# sheet2.net
KiCad netlist of a schematic drawn in Altium Designer
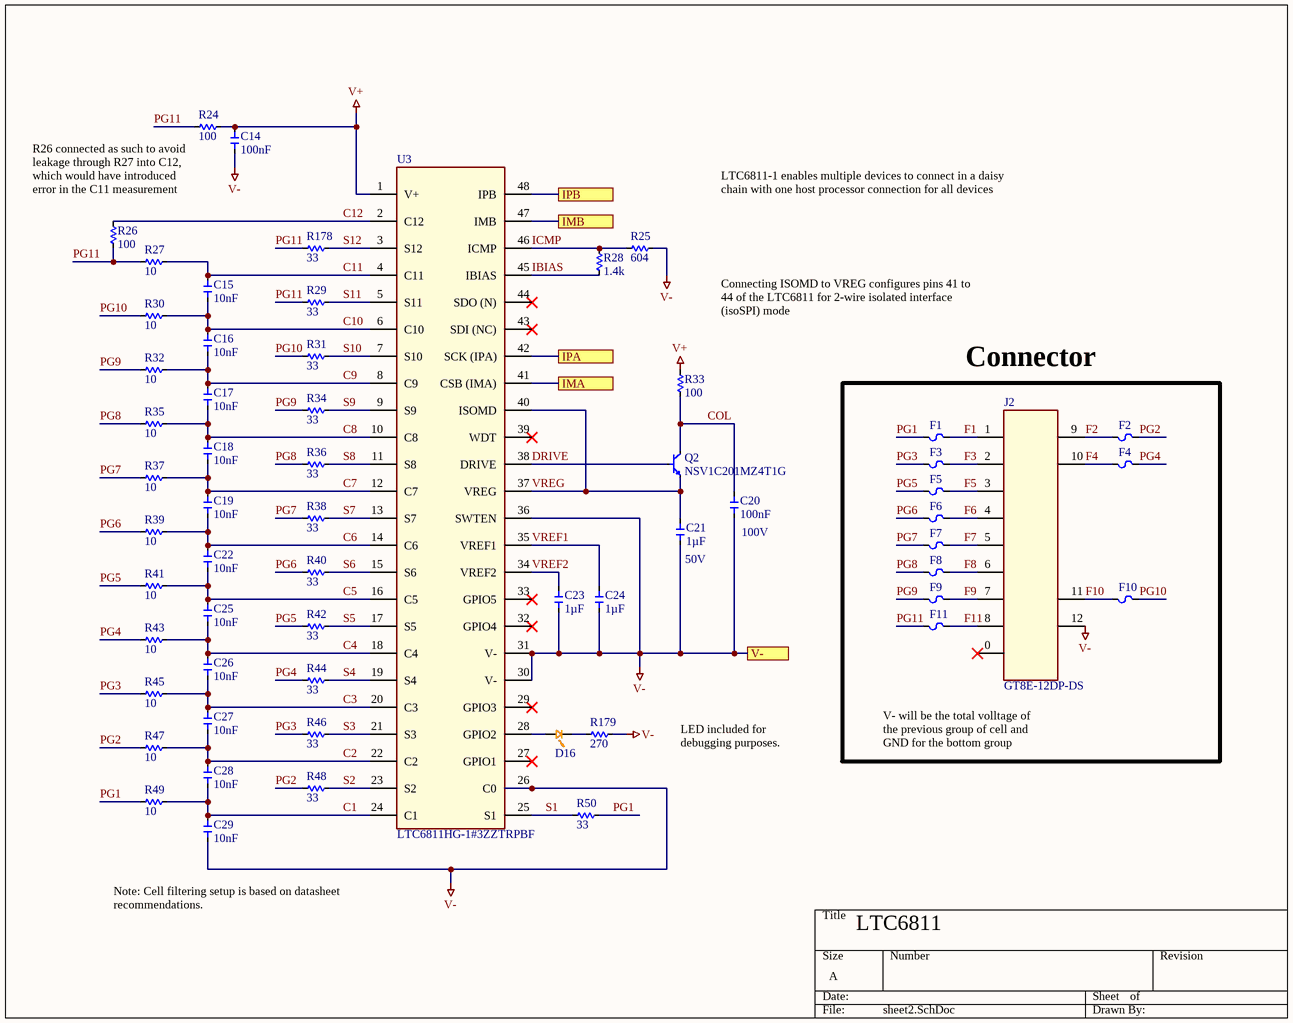
[diagram p0: sheet2.SchDoc]

(export (version "E")
  (design (tool "Eeschema 10.0.6"))
  (components
    (comp (ref "C14")
      (value "100nF")
      (footprint "C0603_0.80MM")
      (description "CAP CER 0.1UF 100V X7S 0603")
      (fields
        (field (name "MANUFACTURER PART NUMBER") "CGJ3E3X7S2A104K080AA")
        (field (name "MANUFACTURER") "TDK Corporation")
      )
      (libsource (lib "Stanford Solar Car Project") (part "2pin_nonpolar_capacitor"))
    )
    (comp (ref "C15")
      (value "10nF")
      (footprint "C0603_0.90MM")
      (description "CAP CER 10000PF 50V C0G 0603")
      (fields (field (name "MANUFACTURER") "TDK Corporation") (field (name "TOLERANCE") "5%"))
      (libsource (lib "Stanford Solar Car Project") (part "2pin_nonpolar_capacitor"))
    )
    (comp (ref "C16")
      (value "10nF")
      (footprint "C0603_0.90MM")
      (description "CAP CER 10000PF 50V C0G 0603")
      (fields (field (name "MANUFACTURER") "TDK Corporation") (field (name "TOLERANCE") "5%"))
      (libsource (lib "Stanford Solar Car Project") (part "2pin_nonpolar_capacitor"))
    )
    (comp (ref "C17")
      (value "10nF")
      (footprint "C0603_0.90MM")
      (description "CAP CER 10000PF 50V C0G 0603")
      (fields (field (name "MANUFACTURER") "TDK Corporation") (field (name "TOLERANCE") "5%"))
      (libsource (lib "Stanford Solar Car Project") (part "2pin_nonpolar_capacitor"))
    )
    (comp (ref "C18")
      (value "10nF")
      (footprint "C0603_0.90MM")
      (description "CAP CER 10000PF 50V C0G 0603")
      (fields (field (name "MANUFACTURER") "TDK Corporation") (field (name "TOLERANCE") "5%"))
      (libsource (lib "Stanford Solar Car Project") (part "2pin_nonpolar_capacitor"))
    )
    (comp (ref "C19")
      (value "10nF")
      (footprint "C0603_0.90MM")
      (description "CAP CER 10000PF 50V C0G 0603")
      (fields (field (name "MANUFACTURER") "TDK Corporation") (field (name "TOLERANCE") "5%"))
      (libsource (lib "Stanford Solar Car Project") (part "2pin_nonpolar_capacitor"))
    )
    (comp (ref "C20")
      (value "100nF")
      (footprint "C0603_0.80MM")
      (description "CAP CER 0.1UF 100V X7S 0603")
      (fields
        (field (name "VOLTAGE - RATED") "100V")
        (field (name "MANUFACTURER PART NUMBER") "CGJ3E3X7S2A104K080AA")
        (field (name "MANUFACTURER") "TDK Corporation")
      )
      (libsource (lib "Stanford Solar Car Project") (part "2pin_nonpolar_capacitor"))
    )
    (comp (ref "C21")
      (value "1µF")
      (footprint "C0805_1.45MM")
      (description "CAP CER 1UF 50V X5R 0805")
      (fields
        (field (name "VOLTAGE - RATED") "50V")
        (field (name "MANUFACTURER") "TDK Corporation")
        (field (name "DIGI-KEY PART NUMBER") "445-12703-1-ND")
      )
      (libsource (lib "Stanford Solar Car Project") (part "2pin_nonpolar_capacitor"))
    )
    (comp (ref "C22")
      (value "10nF")
      (footprint "C0603_0.90MM")
      (description "CAP CER 10000PF 50V C0G 0603")
      (fields (field (name "MANUFACTURER") "TDK Corporation") (field (name "TOLERANCE") "5%"))
      (libsource (lib "Stanford Solar Car Project") (part "2pin_nonpolar_capacitor"))
    )
    (comp (ref "C23")
      (value "1µF")
      (footprint "C0805_1.45MM")
      (description "CAP CER 1UF 50V X5R 0805")
      (fields
        (field (name "MANUFACTURER") "TDK Corporation")
        (field (name "DIGI-KEY PART NUMBER") "445-12703-1-ND")
      )
      (libsource (lib "Stanford Solar Car Project") (part "2pin_nonpolar_capacitor"))
    )
    (comp (ref "C24")
      (value "1µF")
      (footprint "C0805_1.45MM")
      (description "CAP CER 1UF 50V X5R 0805")
      (fields
        (field (name "MANUFACTURER") "TDK Corporation")
        (field (name "DIGI-KEY PART NUMBER") "445-12703-1-ND")
      )
      (libsource (lib "Stanford Solar Car Project") (part "2pin_nonpolar_capacitor"))
    )
    (comp (ref "C25")
      (value "10nF")
      (footprint "C0603_0.90MM")
      (description "CAP CER 10000PF 50V C0G 0603")
      (fields (field (name "MANUFACTURER") "TDK Corporation") (field (name "TOLERANCE") "5%"))
      (libsource (lib "Stanford Solar Car Project") (part "2pin_nonpolar_capacitor"))
    )
    (comp (ref "C26")
      (value "10nF")
      (footprint "C0603_0.90MM")
      (description "CAP CER 10000PF 50V C0G 0603")
      (fields (field (name "MANUFACTURER") "TDK Corporation") (field (name "TOLERANCE") "5%"))
      (libsource (lib "Stanford Solar Car Project") (part "2pin_nonpolar_capacitor"))
    )
    (comp (ref "C27")
      (value "10nF")
      (footprint "C0603_0.90MM")
      (description "CAP CER 10000PF 50V C0G 0603")
      (fields (field (name "MANUFACTURER") "TDK Corporation") (field (name "TOLERANCE") "5%"))
      (libsource (lib "Stanford Solar Car Project") (part "2pin_nonpolar_capacitor"))
    )
    (comp (ref "C28")
      (value "10nF")
      (footprint "C0603_0.90MM")
      (description "CAP CER 10000PF 50V C0G 0603")
      (fields (field (name "MANUFACTURER") "TDK Corporation") (field (name "TOLERANCE") "5%"))
      (libsource (lib "Stanford Solar Car Project") (part "2pin_nonpolar_capacitor"))
    )
    (comp (ref "C29")
      (value "10nF")
      (footprint "C0603_0.90MM")
      (description "CAP CER 10000PF 50V C0G 0603")
      (fields (field (name "MANUFACTURER") "TDK Corporation") (field (name "TOLERANCE") "5%"))
      (libsource (lib "Stanford Solar Car Project") (part "2pin_nonpolar_capacitor"))
    )
    (comp (ref "D16")
      (value "LTST-C194KFKT")
      (footprint "LED_0603P_ORANGE")
      (description "LED ORANGE CLEAR SMD")
      (libsource (lib "Stanford Solar Car Project") (part "_template_led_orange"))
    )
    (comp (ref "F1")
      (value "C2Q 250")
      (footprint "R0603_0.50MM")
      (description "FUSE BOARD MNT 250MA 32VAC 63VDC")
      (fields
        (field (name "MANUFACTURER") "Bel Fuse Inc.")
        (field (name "DIGI-KEY PART NUMBER") "507-1086-1-ND")
      )
      (libsource (lib "sscp") (part "_template_fuse"))
    )
    (comp (ref "F2")
      (value "C2Q 250")
      (footprint "R0603_0.50MM")
      (description "FUSE BOARD MNT 250MA 32VAC 63VDC")
      (fields
        (field (name "MANUFACTURER") "Bel Fuse Inc.")
        (field (name "DIGI-KEY PART NUMBER") "507-1086-1-ND")
      )
      (libsource (lib "sscp") (part "_template_fuse"))
    )
    (comp (ref "F3")
      (value "C2Q 250")
      (footprint "R0603_0.50MM")
      (description "FUSE BOARD MNT 250MA 32VAC 63VDC")
      (fields
        (field (name "MANUFACTURER") "Bel Fuse Inc.")
        (field (name "DIGI-KEY PART NUMBER") "507-1086-1-ND")
      )
      (libsource (lib "sscp") (part "_template_fuse"))
    )
    (comp (ref "F4")
      (value "C2Q 250")
      (footprint "R0603_0.50MM")
      (description "FUSE BOARD MNT 250MA 32VAC 63VDC")
      (fields
        (field (name "MANUFACTURER") "Bel Fuse Inc.")
        (field (name "DIGI-KEY PART NUMBER") "507-1086-1-ND")
      )
      (libsource (lib "sscp") (part "_template_fuse"))
    )
    (comp (ref "F5")
      (value "C2Q 250")
      (footprint "R0603_0.50MM")
      (description "FUSE BOARD MNT 250MA 32VAC 63VDC")
      (fields
        (field (name "MANUFACTURER") "Bel Fuse Inc.")
        (field (name "DIGI-KEY PART NUMBER") "507-1086-1-ND")
      )
      (libsource (lib "sscp") (part "_template_fuse"))
    )
    (comp (ref "F6")
      (value "C2Q 250")
      (footprint "R0603_0.50MM")
      (description "FUSE BOARD MNT 250MA 32VAC 63VDC")
      (fields
        (field (name "MANUFACTURER") "Bel Fuse Inc.")
        (field (name "DIGI-KEY PART NUMBER") "507-1086-1-ND")
      )
      (libsource (lib "sscp") (part "_template_fuse"))
    )
    (comp (ref "F7")
      (value "C2Q 250")
      (footprint "R0603_0.50MM")
      (description "FUSE BOARD MNT 250MA 32VAC 63VDC")
      (fields
        (field (name "MANUFACTURER") "Bel Fuse Inc.")
        (field (name "DIGI-KEY PART NUMBER") "507-1086-1-ND")
      )
      (libsource (lib "sscp") (part "_template_fuse"))
    )
    (comp (ref "F8")
      (value "C2Q 250")
      (footprint "R0603_0.50MM")
      (description "FUSE BOARD MNT 250MA 32VAC 63VDC")
      (fields
        (field (name "MANUFACTURER") "Bel Fuse Inc.")
        (field (name "DIGI-KEY PART NUMBER") "507-1086-1-ND")
      )
      (libsource (lib "sscp") (part "_template_fuse"))
    )
    (comp (ref "F9")
      (value "C2Q 250")
      (footprint "R0603_0.50MM")
      (description "FUSE BOARD MNT 250MA 32VAC 63VDC")
      (fields
        (field (name "MANUFACTURER") "Bel Fuse Inc.")
        (field (name "DIGI-KEY PART NUMBER") "507-1086-1-ND")
      )
      (libsource (lib "sscp") (part "_template_fuse"))
    )
    (comp (ref "F10")
      (value "C2Q 250")
      (footprint "R0603_0.50MM")
      (description "FUSE BOARD MNT 250MA 32VAC 63VDC")
      (fields
        (field (name "MANUFACTURER") "Bel Fuse Inc.")
        (field (name "DIGI-KEY PART NUMBER") "507-1086-1-ND")
      )
      (libsource (lib "sscp") (part "_template_fuse"))
    )
    (comp (ref "F11")
      (value "C2Q 250")
      (footprint "R0603_0.50MM")
      (description "FUSE BOARD MNT 250MA 32VAC 63VDC")
      (fields
        (field (name "MANUFACTURER") "Bel Fuse Inc.")
        (field (name "DIGI-KEY PART NUMBER") "507-1086-1-ND")
      )
      (libsource (lib "sscp") (part "_template_fuse"))
    )
    (comp (ref "J2")
      (value "GT8E-12DP-DS")
      (footprint "GT8E-12DP-DS")
      (description "CONN HEADER R/A 12POS 2MM")
      (fields
        (field (name "MANUFACTURER") "Hirose Electric Co Ltd")
        (field (name "MANUFACTURER PART NUMBER") "GT8E-12DP-DS")
        (field (name "DIGI-KEY PART NUMBER") "H122078-ND")
      )
      (libsource (lib "sscp") (part "CONN_GT8E-12DP-DS"))
    )
    (comp (ref "Q2")
      (value "NSV1C201MZ4T1G")
      (footprint "NPN")
      (description "TRANS NPN 100V 2A SOT223-4")
      (fields
        (field (name "MANUFACTURER") "ON Semiconductor")
        (field (name "DIGI-KEY PART NUMBER") "NSV1C201MZ4T1GOSCT-ND")
      )
      (libsource (lib "Stanford Solar Car Project") (part "_generic_npn"))
    )
    (comp (ref "R24")
      (value "100")
      (footprint "R0805_0.70MM")
      (description "RES SMD 100 OHM 1% 1/2W 0805")
      (fields (field (name "TOLERANCE") "1%") (field (name "MANUFACTURER PART NUMBER") "ERJ-P06F1000V"))
      (libsource (lib "Stanford Solar Car Project") (part "2pin_resistor"))
    )
    (comp (ref "R25")
      (value "604")
      (footprint "R0603_0.55MM")
      (description "RES SMD 604 OHM 1% 1/10W 0603")
      (fields (field (name "DIGI-KEY PART NUMBER") "P604HCT-ND") (field (name "TOLERANCE") "1%"))
      (libsource (lib "Stanford Solar Car Project") (part "2pin_resistor"))
    )
    (comp (ref "R26")
      (value "100")
      (footprint "R0603_0.55MM")
      (description "RES SMD 100 OHM 1% 1/10W 0603")
      (fields
        (field (name "MANUFACTURER PART NUMBER") "ERJ-3EKF1000V")
        (field (name "DIGI-KEY PART NUMBER") "P100HCT-ND")
      )
      (libsource (lib "Stanford Solar Car Project") (part "2pin_resistor"))
    )
    (comp (ref "R27")
      (value "10")
      (footprint "R0603_0.55MM")
      (description "RES SMD 10 OHM 1% 1/4W 0603")
      (fields (field (name "MANUFACTURER") "Panasonic Electronic Components") (field (name "TOLERANCE") "1%"))
      (libsource (lib "Stanford Solar Car Project") (part "2pin_resistor"))
    )
    (comp (ref "R28")
      (value "1.4k")
      (footprint "R0603_0.55MM")
      (description "RES SMD 1.4K OHM 1% 1/10W 0603")
      (fields (field (name "TOLERANCE") "1%") (field (name "MANUFACTURER PART NUMBER") "ERJ-3EKF1401V"))
      (libsource (lib "Stanford Solar Car Project") (part "2pin_resistor"))
    )
    (comp (ref "R29")
      (value "33")
      (footprint "R0603_0.55MM")
      (description "RES SMD 33 OHM 1% 1/4W 0603")
      (fields
        (field (name "MANUFACTURER") "Panasonic Electronic Components")
        (field (name "MANUFACTURER PART NUMBER") "ERJ-PA3F33R0V")
      )
      (libsource (lib "Stanford Solar Car Project") (part "2pin_resistor"))
    )
    (comp (ref "R30")
      (value "10")
      (footprint "R0603_0.55MM")
      (description "RES SMD 10 OHM 1% 1/4W 0603")
      (fields (field (name "MANUFACTURER") "Panasonic Electronic Components") (field (name "TOLERANCE") "1%"))
      (libsource (lib "Stanford Solar Car Project") (part "2pin_resistor"))
    )
    (comp (ref "R31")
      (value "33")
      (footprint "R0603_0.55MM")
      (description "RES SMD 33 OHM 1% 1/4W 0603")
      (fields
        (field (name "MANUFACTURER") "Panasonic Electronic Components")
        (field (name "MANUFACTURER PART NUMBER") "ERJ-PA3F33R0V")
      )
      (libsource (lib "Stanford Solar Car Project") (part "2pin_resistor"))
    )
    (comp (ref "R32")
      (value "10")
      (footprint "R0603_0.55MM")
      (description "RES SMD 10 OHM 1% 1/4W 0603")
      (fields (field (name "MANUFACTURER") "Panasonic Electronic Components") (field (name "TOLERANCE") "1%"))
      (libsource (lib "Stanford Solar Car Project") (part "2pin_resistor"))
    )
    (comp (ref "R33")
      (value "100")
      (footprint "R0603_0.55MM")
      (description "RES SMD 100 OHM 1% 1/4W 0603")
      (fields (field (name "MANUFACTURER PART NUMBER") "ERJ-PA3F1000V") (field (name "TOLERANCE") "1%"))
      (libsource (lib "Stanford Solar Car Project") (part "2pin_resistor"))
    )
    (comp (ref "R34")
      (value "33")
      (footprint "R0603_0.55MM")
      (description "RES SMD 33 OHM 1% 1/4W 0603")
      (fields
        (field (name "MANUFACTURER") "Panasonic Electronic Components")
        (field (name "MANUFACTURER PART NUMBER") "ERJ-PA3F33R0V")
      )
      (libsource (lib "Stanford Solar Car Project") (part "2pin_resistor"))
    )
    (comp (ref "R35")
      (value "10")
      (footprint "R0603_0.55MM")
      (description "RES SMD 10 OHM 1% 1/4W 0603")
      (fields (field (name "MANUFACTURER") "Panasonic Electronic Components") (field (name "TOLERANCE") "1%"))
      (libsource (lib "Stanford Solar Car Project") (part "2pin_resistor"))
    )
    (comp (ref "R36")
      (value "33")
      (footprint "R0603_0.55MM")
      (description "RES SMD 33 OHM 1% 1/4W 0603")
      (fields
        (field (name "MANUFACTURER") "Panasonic Electronic Components")
        (field (name "MANUFACTURER PART NUMBER") "ERJ-PA3F33R0V")
      )
      (libsource (lib "Stanford Solar Car Project") (part "2pin_resistor"))
    )
    (comp (ref "R37")
      (value "10")
      (footprint "R0603_0.55MM")
      (description "RES SMD 10 OHM 1% 1/4W 0603")
      (fields (field (name "MANUFACTURER") "Panasonic Electronic Components") (field (name "TOLERANCE") "1%"))
      (libsource (lib "Stanford Solar Car Project") (part "2pin_resistor"))
    )
    (comp (ref "R38")
      (value "33")
      (footprint "R0603_0.55MM")
      (description "RES SMD 33 OHM 1% 1/4W 0603")
      (fields
        (field (name "MANUFACTURER") "Panasonic Electronic Components")
        (field (name "MANUFACTURER PART NUMBER") "ERJ-PA3F33R0V")
      )
      (libsource (lib "Stanford Solar Car Project") (part "2pin_resistor"))
    )
    (comp (ref "R39")
      (value "10")
      (footprint "R0603_0.55MM")
      (description "RES SMD 10 OHM 1% 1/4W 0603")
      (fields (field (name "MANUFACTURER") "Panasonic Electronic Components") (field (name "TOLERANCE") "1%"))
      (libsource (lib "Stanford Solar Car Project") (part "2pin_resistor"))
    )
    (comp (ref "R40")
      (value "33")
      (footprint "R0603_0.55MM")
      (description "RES SMD 33 OHM 1% 1/4W 0603")
      (fields
        (field (name "MANUFACTURER") "Panasonic Electronic Components")
        (field (name "MANUFACTURER PART NUMBER") "ERJ-PA3F33R0V")
      )
      (libsource (lib "Stanford Solar Car Project") (part "2pin_resistor"))
    )
    (comp (ref "R41")
      (value "10")
      (footprint "R0603_0.55MM")
      (description "RES SMD 10 OHM 1% 1/4W 0603")
      (fields (field (name "MANUFACTURER") "Panasonic Electronic Components") (field (name "TOLERANCE") "1%"))
      (libsource (lib "Stanford Solar Car Project") (part "2pin_resistor"))
    )
    (comp (ref "R42")
      (value "33")
      (footprint "R0603_0.55MM")
      (description "RES SMD 33 OHM 1% 1/4W 0603")
      (fields
        (field (name "MANUFACTURER") "Panasonic Electronic Components")
        (field (name "MANUFACTURER PART NUMBER") "ERJ-PA3F33R0V")
      )
      (libsource (lib "Stanford Solar Car Project") (part "2pin_resistor"))
    )
    (comp (ref "R43")
      (value "10")
      (footprint "R0603_0.55MM")
      (description "RES SMD 10 OHM 1% 1/4W 0603")
      (fields (field (name "MANUFACTURER") "Panasonic Electronic Components") (field (name "TOLERANCE") "1%"))
      (libsource (lib "Stanford Solar Car Project") (part "2pin_resistor"))
    )
    (comp (ref "R44")
      (value "33")
      (footprint "R0603_0.55MM")
      (description "RES SMD 33 OHM 1% 1/4W 0603")
      (fields
        (field (name "MANUFACTURER") "Panasonic Electronic Components")
        (field (name "MANUFACTURER PART NUMBER") "ERJ-PA3F33R0V")
      )
      (libsource (lib "Stanford Solar Car Project") (part "2pin_resistor"))
    )
    (comp (ref "R45")
      (value "10")
      (footprint "R0603_0.55MM")
      (description "RES SMD 10 OHM 1% 1/4W 0603")
      (fields (field (name "MANUFACTURER") "Panasonic Electronic Components") (field (name "TOLERANCE") "1%"))
      (libsource (lib "Stanford Solar Car Project") (part "2pin_resistor"))
    )
    (comp (ref "R46")
      (value "33")
      (footprint "R0603_0.55MM")
      (description "RES SMD 33 OHM 1% 1/4W 0603")
      (fields
        (field (name "MANUFACTURER") "Panasonic Electronic Components")
        (field (name "MANUFACTURER PART NUMBER") "ERJ-PA3F33R0V")
      )
      (libsource (lib "Stanford Solar Car Project") (part "2pin_resistor"))
    )
    (comp (ref "R47")
      (value "10")
      (footprint "R0603_0.55MM")
      (description "RES SMD 10 OHM 1% 1/4W 0603")
      (fields (field (name "MANUFACTURER") "Panasonic Electronic Components") (field (name "TOLERANCE") "1%"))
      (libsource (lib "Stanford Solar Car Project") (part "2pin_resistor"))
    )
    (comp (ref "R48")
      (value "33")
      (footprint "R0603_0.55MM")
      (description "RES SMD 33 OHM 1% 1/4W 0603")
      (fields
        (field (name "MANUFACTURER") "Panasonic Electronic Components")
        (field (name "MANUFACTURER PART NUMBER") "ERJ-PA3F33R0V")
      )
      (libsource (lib "Stanford Solar Car Project") (part "2pin_resistor"))
    )
    (comp (ref "R49")
      (value "10")
      (footprint "R0603_0.55MM")
      (description "RES SMD 10 OHM 1% 1/4W 0603")
      (fields (field (name "MANUFACTURER") "Panasonic Electronic Components") (field (name "TOLERANCE") "1%"))
      (libsource (lib "Stanford Solar Car Project") (part "2pin_resistor"))
    )
    (comp (ref "R50")
      (value "33")
      (footprint "R0603_0.55MM")
      (description "RES SMD 33 OHM 1% 1/4W 0603")
      (fields
        (field (name "MANUFACTURER") "Panasonic Electronic Components")
        (field (name "MANUFACTURER PART NUMBER") "ERJ-PA3F33R0V")
      )
      (libsource (lib "Stanford Solar Car Project") (part "2pin_resistor"))
    )
    (comp (ref "R178")
      (value "33")
      (footprint "R0603_0.55MM")
      (description "RES SMD 33 OHM 1% 1/4W 0603")
      (fields
        (field (name "MANUFACTURER") "Panasonic Electronic Components")
        (field (name "MANUFACTURER PART NUMBER") "ERJ-PA3F33R0V")
      )
      (libsource (lib "Stanford Solar Car Project") (part "2pin_resistor"))
    )
    (comp (ref "R179")
      (value "270")
      (footprint "R0603_0.55MM")
      (description "RES SMD 270 OHM 1% 1/4W 0603")
      (fields (field (name "TOLERANCE") "1%") (field (name "DIGI-KEY PART NUMBER") "P270BYCT-ND"))
      (libsource (lib "Stanford Solar Car Project") (part "2pin_resistor"))
    )
    (comp (ref "U3")
      (value "LTC6811HG-1#3ZZTRPBF")
      (footprint "48TSSOP50")
      (description "MULTICELL BAT MON S")
      (fields
        (field (name "DIGI-KEY PART NUMBER") "LTC6811HG-1#3ZZTRPBFCT-ND")
        (field (name "MANUFACTURER") "Linear Technology/Analog Devices")
      )
      (libsource (lib "Stanford Solar Car Project") (part "IC_LTC6811"))
    )
  )
  (nets
    (net (code "1") (name "/C1") (class "Default")
      (node (ref "C28") (pin "1") (pintype "passive"))
      (node (ref "C29") (pin "2") (pintype "passive"))
      (node (ref "R49") (pin "2") (pintype "passive"))
      (node (ref "U3") (pin "24") (pinfunction "C1_24") (pintype "passive"))
    )
    (net (code "2") (name "/C2") (class "Default")
      (node (ref "C27") (pin "1") (pintype "passive"))
      (node (ref "C28") (pin "2") (pintype "passive"))
      (node (ref "R47") (pin "2") (pintype "passive"))
      (node (ref "U3") (pin "22") (pinfunction "C2_22") (pintype "passive"))
    )
    (net (code "3") (name "/C3") (class "Default")
      (node (ref "C26") (pin "1") (pintype "passive"))
      (node (ref "C27") (pin "2") (pintype "passive"))
      (node (ref "R45") (pin "2") (pintype "passive"))
      (node (ref "U3") (pin "20") (pinfunction "C3_20") (pintype "passive"))
    )
    (net (code "4") (name "/C4") (class "Default")
      (node (ref "C25") (pin "1") (pintype "passive"))
      (node (ref "C26") (pin "2") (pintype "passive"))
      (node (ref "R43") (pin "2") (pintype "passive"))
      (node (ref "U3") (pin "18") (pinfunction "C4_18") (pintype "passive"))
    )
    (net (code "5") (name "/C5") (class "Default")
      (node (ref "C22") (pin "1") (pintype "passive"))
      (node (ref "C25") (pin "2") (pintype "passive"))
      (node (ref "R41") (pin "2") (pintype "passive"))
      (node (ref "U3") (pin "16") (pinfunction "C5_16") (pintype "passive"))
    )
    (net (code "6") (name "/C6") (class "Default")
      (node (ref "C19") (pin "1") (pintype "passive"))
      (node (ref "C22") (pin "2") (pintype "passive"))
      (node (ref "R39") (pin "2") (pintype "passive"))
      (node (ref "U3") (pin "14") (pinfunction "C6_14") (pintype "passive"))
    )
    (net (code "7") (name "/C7") (class "Default")
      (node (ref "C18") (pin "1") (pintype "passive"))
      (node (ref "C19") (pin "2") (pintype "passive"))
      (node (ref "R37") (pin "2") (pintype "passive"))
      (node (ref "U3") (pin "12") (pinfunction "C7_12") (pintype "passive"))
    )
    (net (code "8") (name "/C8") (class "Default")
      (node (ref "C17") (pin "1") (pintype "passive"))
      (node (ref "C18") (pin "2") (pintype "passive"))
      (node (ref "R35") (pin "2") (pintype "passive"))
      (node (ref "U3") (pin "10") (pinfunction "C8_10") (pintype "passive"))
    )
    (net (code "9") (name "/C9") (class "Default")
      (node (ref "C16") (pin "1") (pintype "passive"))
      (node (ref "C17") (pin "2") (pintype "passive"))
      (node (ref "R32") (pin "2") (pintype "passive"))
      (node (ref "U3") (pin "8") (pinfunction "C9_8") (pintype "passive"))
    )
    (net (code "10") (name "/C10") (class "Default")
      (node (ref "C15") (pin "1") (pintype "passive"))
      (node (ref "C16") (pin "2") (pintype "passive"))
      (node (ref "R30") (pin "2") (pintype "passive"))
      (node (ref "U3") (pin "6") (pinfunction "C10_6") (pintype "passive"))
    )
    (net (code "11") (name "/C11") (class "Default")
      (node (ref "C15") (pin "2") (pintype "passive"))
      (node (ref "R27") (pin "2") (pintype "passive"))
      (node (ref "U3") (pin "4") (pinfunction "C11_4") (pintype "passive"))
    )
    (net (code "12") (name "/C12") (class "Default")
      (node (ref "R26") (pin "2") (pintype "passive"))
      (node (ref "U3") (pin "2") (pinfunction "C12_2") (pintype "passive"))
    )
    (net (code "13") (name "/COL") (class "Default")
      (node (ref "C20") (pin "1") (pintype "passive"))
      (node (ref "Q2") (pin "2") (pintype "passive"))
      (node (ref "R33") (pin "2") (pintype "passive"))
    )
    (net (code "14") (name "/DRIVE") (class "Default")
      (node (ref "Q2") (pin "1") (pintype "passive"))
      (node (ref "U3") (pin "38") (pinfunction "DRIVE_38") (pintype "passive"))
    )
    (net (code "15") (name "/F1") (class "Default")
      (node (ref "F1") (pin "2") (pintype "passive"))
      (node (ref "J2") (pin "1") (pinfunction "1_1") (pintype "passive"))
    )
    (net (code "16") (name "/F2") (class "Default")
      (node (ref "F2") (pin "1") (pintype "passive"))
      (node (ref "J2") (pin "9") (pinfunction "9_9") (pintype "passive"))
    )
    (net (code "17") (name "/F3") (class "Default")
      (node (ref "F3") (pin "2") (pintype "passive"))
      (node (ref "J2") (pin "2") (pinfunction "2_2") (pintype "passive"))
    )
    (net (code "18") (name "/F4") (class "Default")
      (node (ref "F4") (pin "1") (pintype "passive"))
      (node (ref "J2") (pin "10") (pinfunction "10_10") (pintype "passive"))
    )
    (net (code "19") (name "/F5") (class "Default")
      (node (ref "F5") (pin "2") (pintype "passive"))
      (node (ref "J2") (pin "3") (pinfunction "3_3") (pintype "passive"))
    )
    (net (code "20") (name "/F6") (class "Default")
      (node (ref "F6") (pin "2") (pintype "passive"))
      (node (ref "J2") (pin "4") (pinfunction "4_4") (pintype "passive"))
    )
    (net (code "21") (name "/F7") (class "Default")
      (node (ref "F7") (pin "2") (pintype "passive"))
      (node (ref "J2") (pin "5") (pinfunction "5_5") (pintype "passive"))
    )
    (net (code "22") (name "/F8") (class "Default")
      (node (ref "F8") (pin "2") (pintype "passive"))
      (node (ref "J2") (pin "6") (pinfunction "6_6") (pintype "passive"))
    )
    (net (code "23") (name "/F9") (class "Default")
      (node (ref "F9") (pin "2") (pintype "passive"))
      (node (ref "J2") (pin "7") (pinfunction "7_7") (pintype "passive"))
    )
    (net (code "24") (name "/F10") (class "Default")
      (node (ref "F10") (pin "1") (pintype "passive"))
      (node (ref "J2") (pin "11") (pinfunction "11_11") (pintype "passive"))
    )
    (net (code "25") (name "/F11") (class "Default")
      (node (ref "F11") (pin "2") (pintype "passive"))
      (node (ref "J2") (pin "8") (pinfunction "8_8") (pintype "passive"))
    )
    (net (code "26") (name "/IBIAS") (class "Default")
      (node (ref "R28") (pin "2") (pintype "passive"))
      (node (ref "U3") (pin "45") (pinfunction "IBIAS_45") (pintype "passive"))
    )
    (net (code "27") (name "/ICMP") (class "Default")
      (node (ref "R25") (pin "1") (pintype "passive"))
      (node (ref "R28") (pin "1") (pintype "passive"))
      (node (ref "U3") (pin "46") (pinfunction "ICMP_46") (pintype "passive"))
    )
    (net (code "28") (name "/IMA") (class "Default")
      (node (ref "U3") (pin "41") (pinfunction "CSB_(IMA)_41") (pintype "passive"))
    )
    (net (code "29") (name "/IMB") (class "Default")
      (node (ref "U3") (pin "47") (pinfunction "IMB_47") (pintype "passive"))
    )
    (net (code "30") (name "/IPA") (class "Default")
      (node (ref "U3") (pin "42") (pinfunction "SCK_(IPA)_42") (pintype "passive"))
    )
    (net (code "31") (name "/IPB") (class "Default")
      (node (ref "U3") (pin "48") (pinfunction "IPB_48") (pintype "passive"))
    )
    (net (code "32") (name "/PG1") (class "Default")
      (node (ref "F1") (pin "1") (pintype "passive"))
      (node (ref "R49") (pin "1") (pintype "passive"))
      (node (ref "R50") (pin "2") (pintype "passive"))
    )
    (net (code "33") (name "/PG2") (class "Default")
      (node (ref "F2") (pin "2") (pintype "passive"))
      (node (ref "R47") (pin "1") (pintype "passive"))
      (node (ref "R48") (pin "1") (pintype "passive"))
    )
    (net (code "34") (name "/PG3") (class "Default")
      (node (ref "F3") (pin "1") (pintype "passive"))
      (node (ref "R45") (pin "1") (pintype "passive"))
      (node (ref "R46") (pin "1") (pintype "passive"))
    )
    (net (code "35") (name "/PG4") (class "Default")
      (node (ref "F4") (pin "2") (pintype "passive"))
      (node (ref "R43") (pin "1") (pintype "passive"))
      (node (ref "R44") (pin "1") (pintype "passive"))
    )
    (net (code "36") (name "/PG5") (class "Default")
      (node (ref "F5") (pin "1") (pintype "passive"))
      (node (ref "R41") (pin "1") (pintype "passive"))
      (node (ref "R42") (pin "1") (pintype "passive"))
    )
    (net (code "37") (name "/PG6") (class "Default")
      (node (ref "F6") (pin "1") (pintype "passive"))
      (node (ref "R39") (pin "1") (pintype "passive"))
      (node (ref "R40") (pin "1") (pintype "passive"))
    )
    (net (code "38") (name "/PG7") (class "Default")
      (node (ref "F7") (pin "1") (pintype "passive"))
      (node (ref "R37") (pin "1") (pintype "passive"))
      (node (ref "R38") (pin "1") (pintype "passive"))
    )
    (net (code "39") (name "/PG8") (class "Default")
      (node (ref "F8") (pin "1") (pintype "passive"))
      (node (ref "R35") (pin "1") (pintype "passive"))
      (node (ref "R36") (pin "1") (pintype "passive"))
    )
    (net (code "40") (name "/PG9") (class "Default")
      (node (ref "F9") (pin "1") (pintype "passive"))
      (node (ref "R32") (pin "1") (pintype "passive"))
      (node (ref "R34") (pin "1") (pintype "passive"))
    )
    (net (code "41") (name "/PG10") (class "Default")
      (node (ref "F10") (pin "2") (pintype "passive"))
      (node (ref "R30") (pin "1") (pintype "passive"))
      (node (ref "R31") (pin "1") (pintype "passive"))
    )
    (net (code "42") (name "/PG11") (class "Default")
      (node (ref "F11") (pin "1") (pintype "passive"))
      (node (ref "R178") (pin "1") (pintype "passive"))
      (node (ref "R24") (pin "1") (pintype "passive"))
      (node (ref "R26") (pin "1") (pintype "passive"))
      (node (ref "R27") (pin "1") (pintype "passive"))
      (node (ref "R29") (pin "1") (pintype "passive"))
    )
    (net (code "43") (name "/S1") (class "Default")
      (node (ref "R50") (pin "1") (pintype "passive"))
      (node (ref "U3") (pin "25") (pinfunction "S1_25") (pintype "passive"))
    )
    (net (code "44") (name "/S2") (class "Default")
      (node (ref "R48") (pin "2") (pintype "passive"))
      (node (ref "U3") (pin "23") (pinfunction "S2_23") (pintype "passive"))
    )
    (net (code "45") (name "/S3") (class "Default")
      (node (ref "R46") (pin "2") (pintype "passive"))
      (node (ref "U3") (pin "21") (pinfunction "S3_21") (pintype "passive"))
    )
    (net (code "46") (name "/S4") (class "Default")
      (node (ref "R44") (pin "2") (pintype "passive"))
      (node (ref "U3") (pin "19") (pinfunction "S4_19") (pintype "passive"))
    )
    (net (code "47") (name "/S5") (class "Default")
      (node (ref "R42") (pin "2") (pintype "passive"))
      (node (ref "U3") (pin "17") (pinfunction "S5_17") (pintype "passive"))
    )
    (net (code "48") (name "/S6") (class "Default")
      (node (ref "R40") (pin "2") (pintype "passive"))
      (node (ref "U3") (pin "15") (pinfunction "S6_15") (pintype "passive"))
    )
    (net (code "49") (name "/S7") (class "Default")
      (node (ref "R38") (pin "2") (pintype "passive"))
      (node (ref "U3") (pin "13") (pinfunction "S7_13") (pintype "passive"))
    )
    (net (code "50") (name "/S8") (class "Default")
      (node (ref "R36") (pin "2") (pintype "passive"))
      (node (ref "U3") (pin "11") (pinfunction "S8_11") (pintype "passive"))
    )
    (net (code "51") (name "/S9") (class "Default")
      (node (ref "R34") (pin "2") (pintype "passive"))
      (node (ref "U3") (pin "9") (pinfunction "S9_9") (pintype "passive"))
    )
    (net (code "52") (name "/S10") (class "Default")
      (node (ref "R31") (pin "2") (pintype "passive"))
      (node (ref "U3") (pin "7") (pinfunction "S10_7") (pintype "passive"))
    )
    (net (code "53") (name "/S11") (class "Default")
      (node (ref "R29") (pin "2") (pintype "passive"))
      (node (ref "U3") (pin "5") (pinfunction "S11_5") (pintype "passive"))
    )
    (net (code "54") (name "/S12") (class "Default")
      (node (ref "R178") (pin "2") (pintype "passive"))
      (node (ref "U3") (pin "3") (pinfunction "S12_3") (pintype "passive"))
    )
    (net (code "55") (name "/VREF1") (class "Default")
      (node (ref "C24") (pin "1") (pintype "passive"))
      (node (ref "U3") (pin "35") (pinfunction "VREF1_35") (pintype "passive"))
    )
    (net (code "56") (name "/VREF2") (class "Default")
      (node (ref "C23") (pin "1") (pintype "passive"))
      (node (ref "U3") (pin "34") (pinfunction "VREF2_34") (pintype "passive"))
    )
    (net (code "57") (name "/VREG") (class "Default")
      (node (ref "C21") (pin "1") (pintype "passive"))
      (node (ref "Q2") (pin "3") (pintype "passive"))
      (node (ref "U3") (pin "37") (pinfunction "VREG_37") (pintype "passive"))
      (node (ref "U3") (pin "40") (pinfunction "ISOMD_40") (pintype "passive"))
    )
    (net (code "58") (name "Net-(D16-Pad1)") (class "Default")
      (node (ref "D16") (pin "1") (pintype "passive"))
      (node (ref "R179") (pin "1") (pintype "passive"))
    )
    (net (code "59") (name "Net-(U3-GPIO2)") (class "Default")
      (node (ref "D16") (pin "2") (pintype "passive"))
      (node (ref "U3") (pin "28") (pinfunction "GPIO2_28") (pintype "passive"))
    )
    (net (code "60") (name "V+") (class "Default")
      (node (ref "C14") (pin "1") (pintype "passive"))
      (node (ref "R24") (pin "2") (pintype "passive"))
      (node (ref "R33") (pin "1") (pintype "passive"))
      (node (ref "U3") (pin "1") (pinfunction "V+_1") (pintype "passive"))
    )
    (net (code "61") (name "V-") (class "Default")
      (node (ref "C14") (pin "2") (pintype "passive"))
      (node (ref "C20") (pin "2") (pintype "passive"))
      (node (ref "C21") (pin "2") (pintype "passive"))
      (node (ref "C23") (pin "2") (pintype "passive"))
      (node (ref "C24") (pin "2") (pintype "passive"))
      (node (ref "C29") (pin "1") (pintype "passive"))
      (node (ref "J2") (pin "12") (pinfunction "12_12") (pintype "passive"))
      (node (ref "R179") (pin "2") (pintype "passive"))
      (node (ref "R25") (pin "2") (pintype "passive"))
      (node (ref "U3") (pin "26") (pinfunction "C0_26") (pintype "passive"))
      (node (ref "U3") (pin "30") (pinfunction "V-_30") (pintype "passive"))
      (node (ref "U3") (pin "31") (pinfunction "V-_31") (pintype "passive"))
      (node (ref "U3") (pin "36") (pinfunction "SWTEN_36") (pintype "passive"))
    )
    (net (code "62") (name "unconnected-(J2-Pad0)") (class "Default")
      (node (ref "J2") (pin "0") (pinfunction "0_0") (pintype "passive+no_connect"))
    )
    (net (code "63") (name "unconnected-(U3-GPIO1-Pad27)") (class "Default")
      (node (ref "U3") (pin "27") (pinfunction "GPIO1_27") (pintype "passive+no_connect"))
    )
    (net (code "64") (name "unconnected-(U3-GPIO3-Pad29)") (class "Default")
      (node (ref "U3") (pin "29") (pinfunction "GPIO3_29") (pintype "passive+no_connect"))
    )
    (net (code "65") (name "unconnected-(U3-GPIO4-Pad32)") (class "Default")
      (node (ref "U3") (pin "32") (pinfunction "GPIO4_32") (pintype "passive+no_connect"))
    )
    (net (code "66") (name "unconnected-(U3-GPIO5-Pad33)") (class "Default")
      (node (ref "U3") (pin "33") (pinfunction "GPIO5_33") (pintype "passive+no_connect"))
    )
    (net (code "67") (name "unconnected-(U3-SDI_(NC)-Pad43)") (class "Default")
      (node (ref "U3") (pin "43") (pinfunction "SDI_(NC)_43") (pintype "passive+no_connect"))
    )
    (net (code "68") (name "unconnected-(U3-SDO_(N)-Pad44)") (class "Default")
      (node (ref "U3") (pin "44") (pinfunction "SDO_(N)_44") (pintype "passive+no_connect"))
    )
    (net (code "69") (name "unconnected-(U3-WDT-Pad39)") (class "Default")
      (node (ref "U3") (pin "39") (pinfunction "WDT_39") (pintype "passive+no_connect"))
    )
  )
)
